# NavCom_Board_2.net
KiCad netlist of a schematic drawn in EAGLE
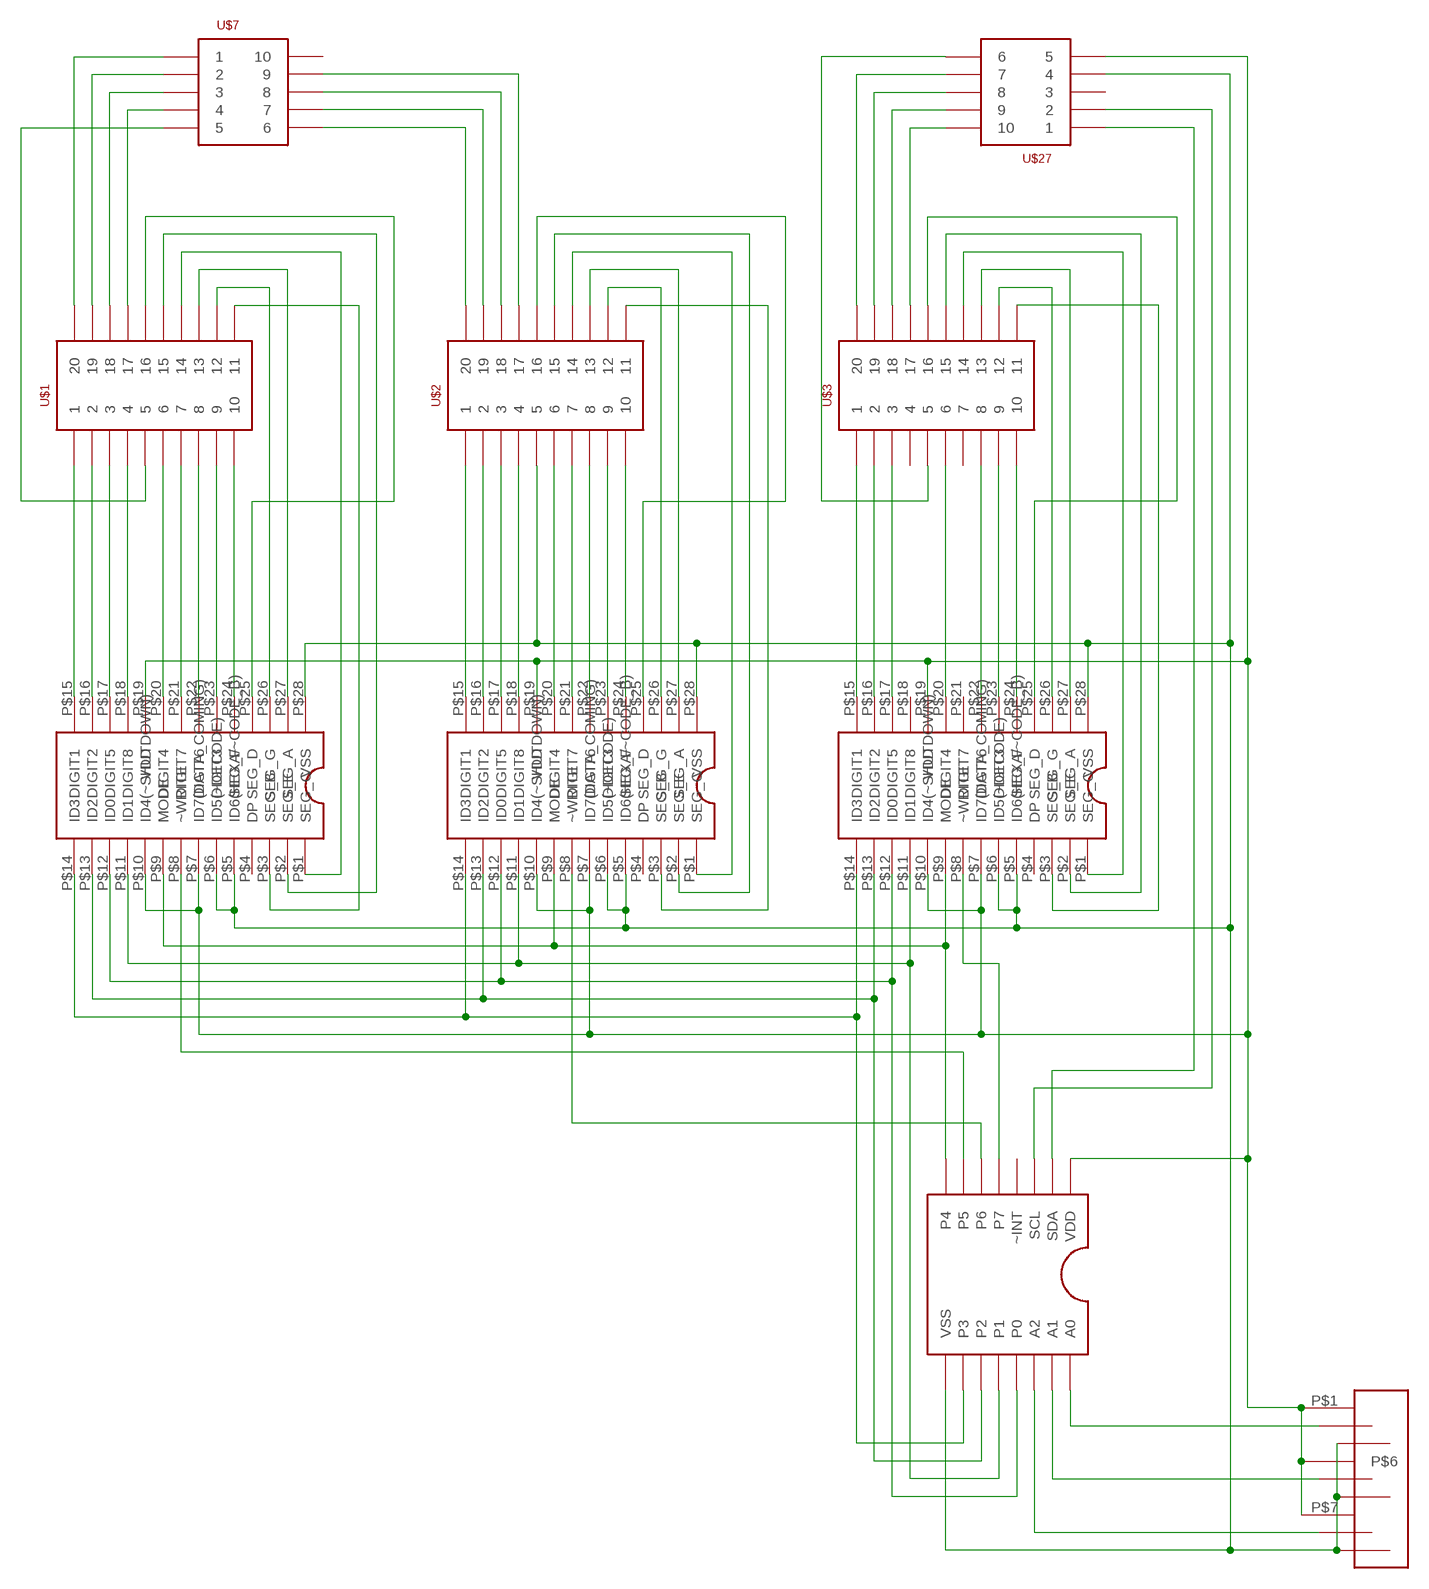
[diagram p0: schematic, sheet 1]

(export (version "E")
  (design (tool "Eeschema 10.0.6"))
  (components
    (comp (ref "U$1")
      (value "LISTA_2X10")
      (footprint "eagle-import:LISTA_2X10")
      (libsource (lib "eagle-import") (part "LISTA_2X10"))
    )
    (comp (ref "U$2")
      (value "LISTA_2X10")
      (footprint "eagle-import:LISTA_2X10")
      (libsource (lib "eagle-import") (part "LISTA_2X10"))
    )
    (comp (ref "U$3")
      (value "LISTA_2X10")
      (footprint "eagle-import:LISTA_2X10")
      (libsource (lib "eagle-import") (part "LISTA_2X10"))
    )
    (comp (ref "U$4")
      (value "ICM7228A")
      (footprint "eagle-import:ICM7228A")
      (libsource (lib "eagle-import") (part "ICM7228A"))
    )
    (comp (ref "U$5")
      (value "ICM7228A")
      (footprint "eagle-import:ICM7228A")
      (libsource (lib "eagle-import") (part "ICM7228A"))
    )
    (comp (ref "U$6")
      (value "ICM7228A")
      (footprint "eagle-import:ICM7228A")
      (libsource (lib "eagle-import") (part "ICM7228A"))
    )
    (comp (ref "U$7")
      (value "LISTA_2X5")
      (footprint "eagle-import:LISTA_2X5")
      (libsource (lib "eagle-import") (part "LISTA_2X5"))
    )
    (comp (ref "U$9")
      (value "PCF8574A")
      (footprint "eagle-import:PCF8574A")
      (libsource (lib "eagle-import") (part "PCF8574A"))
    )
    (comp (ref "U$11")
      (value "ADRESA_0..2")
      (footprint "eagle-import:ADRESA_0..2")
      (libsource (lib "eagle-import") (part "ADRESA_0..2"))
    )
    (comp (ref "U$27")
      (value "LISTA_2X5")
      (footprint "eagle-import:LISTA_2X5")
      (libsource (lib "eagle-import") (part "LISTA_2X5"))
    )
  )
  (nets
    (net (code "1") (name "Net-(U$1-Pad5)") (class "Default")
      (node (ref "U$1") (pin "5") (pinfunction "5_5") (pintype "bidirectional"))
      (node (ref "U$7") (pin "5") (pinfunction "5_5") (pintype "bidirectional"))
    )
    (net (code "2") (name "Net-(U$1-Pad17)") (class "Default")
      (node (ref "U$1") (pin "17") (pinfunction "17_17") (pintype "bidirectional"))
      (node (ref "U$7") (pin "4") (pinfunction "4_4") (pintype "bidirectional"))
    )
    (net (code "3") (name "Net-(U$1-Pad18)") (class "Default")
      (node (ref "U$1") (pin "18") (pinfunction "18_18") (pintype "bidirectional"))
      (node (ref "U$7") (pin "3") (pinfunction "3_3") (pintype "bidirectional"))
    )
    (net (code "4") (name "Net-(U$1-Pad19)") (class "Default")
      (node (ref "U$1") (pin "19") (pinfunction "19_19") (pintype "bidirectional"))
      (node (ref "U$7") (pin "2") (pinfunction "2_2") (pintype "bidirectional"))
    )
    (net (code "5") (name "Net-(U$1-Pad20)") (class "Default")
      (node (ref "U$1") (pin "20") (pinfunction "20_20") (pintype "bidirectional"))
      (node (ref "U$7") (pin "1") (pinfunction "1_1") (pintype "bidirectional"))
    )
    (net (code "6") (name "Net-(U$2-Pad17)") (class "Default")
      (node (ref "U$2") (pin "17") (pinfunction "17_17") (pintype "bidirectional"))
      (node (ref "U$7") (pin "9") (pinfunction "9_9") (pintype "bidirectional"))
    )
    (net (code "7") (name "Net-(U$2-Pad18)") (class "Default")
      (node (ref "U$2") (pin "18") (pinfunction "18_18") (pintype "bidirectional"))
      (node (ref "U$7") (pin "8") (pinfunction "8_8") (pintype "bidirectional"))
    )
    (net (code "8") (name "Net-(U$2-Pad19)") (class "Default")
      (node (ref "U$2") (pin "19") (pinfunction "19_19") (pintype "bidirectional"))
      (node (ref "U$7") (pin "7") (pinfunction "7_7") (pintype "bidirectional"))
    )
    (net (code "9") (name "Net-(U$2-Pad20)") (class "Default")
      (node (ref "U$2") (pin "20") (pinfunction "20_20") (pintype "bidirectional"))
      (node (ref "U$7") (pin "6") (pinfunction "6_6") (pintype "bidirectional"))
    )
    (net (code "10") (name "Net-(U$4-DIGIT1)") (class "Default")
      (node (ref "U$1") (pin "1") (pinfunction "1_1") (pintype "bidirectional"))
      (node (ref "U$4") (pin "P$15") (pinfunction "DIGIT1_P$15") (pintype "bidirectional"))
    )
    (net (code "11") (name "Net-(U$4-DIGIT2)") (class "Default")
      (node (ref "U$1") (pin "2") (pinfunction "2_2") (pintype "bidirectional"))
      (node (ref "U$4") (pin "P$16") (pinfunction "DIGIT2_P$16") (pintype "bidirectional"))
    )
    (net (code "12") (name "Net-(U$4-DIGIT3)") (class "Default")
      (node (ref "U$1") (pin "9") (pinfunction "9_9") (pintype "bidirectional"))
      (node (ref "U$4") (pin "P$23") (pinfunction "DIGIT3_P$23") (pintype "bidirectional"))
    )
    (net (code "13") (name "Net-(U$4-DIGIT4)") (class "Default")
      (node (ref "U$1") (pin "6") (pinfunction "6_6") (pintype "bidirectional"))
      (node (ref "U$4") (pin "P$20") (pinfunction "DIGIT4_P$20") (pintype "bidirectional"))
    )
    (net (code "14") (name "Net-(U$4-DIGIT5)") (class "Default")
      (node (ref "U$1") (pin "3") (pinfunction "3_3") (pintype "bidirectional"))
      (node (ref "U$4") (pin "P$17") (pinfunction "DIGIT5_P$17") (pintype "bidirectional"))
    )
    (net (code "15") (name "Net-(U$4-DIGIT6)") (class "Default")
      (node (ref "U$1") (pin "8") (pinfunction "8_8") (pintype "bidirectional"))
      (node (ref "U$4") (pin "P$22") (pinfunction "DIGIT6_P$22") (pintype "bidirectional"))
    )
    (net (code "16") (name "Net-(U$4-DIGIT7)") (class "Default")
      (node (ref "U$1") (pin "7") (pinfunction "7_7") (pintype "bidirectional"))
      (node (ref "U$4") (pin "P$21") (pinfunction "DIGIT7_P$21") (pintype "bidirectional"))
    )
    (net (code "17") (name "Net-(U$4-DIGIT8)") (class "Default")
      (node (ref "U$1") (pin "4") (pinfunction "4_4") (pintype "bidirectional"))
      (node (ref "U$4") (pin "P$18") (pinfunction "DIGIT8_P$18") (pintype "bidirectional"))
    )
    (net (code "18") (name "Net-(U$4-ID0)") (class "Default")
      (node (ref "U$4") (pin "P$12") (pinfunction "ID0_P$12") (pintype "bidirectional"))
      (node (ref "U$5") (pin "P$12") (pinfunction "ID0_P$12") (pintype "bidirectional"))
      (node (ref "U$6") (pin "P$12") (pinfunction "ID0_P$12") (pintype "bidirectional"))
      (node (ref "U$9") (pin "P0") (pinfunction "P0_P0") (pintype "bidirectional"))
    )
    (net (code "19") (name "Net-(U$4-ID1)") (class "Default")
      (node (ref "U$4") (pin "P$11") (pinfunction "ID1_P$11") (pintype "bidirectional"))
      (node (ref "U$5") (pin "P$11") (pinfunction "ID1_P$11") (pintype "bidirectional"))
      (node (ref "U$6") (pin "P$11") (pinfunction "ID1_P$11") (pintype "bidirectional"))
      (node (ref "U$9") (pin "P1") (pinfunction "P1_P1") (pintype "bidirectional"))
    )
    (net (code "20") (name "Net-(U$4-ID2)") (class "Default")
      (node (ref "U$4") (pin "P$13") (pinfunction "ID2_P$13") (pintype "bidirectional"))
      (node (ref "U$5") (pin "P$13") (pinfunction "ID2_P$13") (pintype "bidirectional"))
      (node (ref "U$6") (pin "P$13") (pinfunction "ID2_P$13") (pintype "bidirectional"))
      (node (ref "U$9") (pin "P2") (pinfunction "P2_P2") (pintype "bidirectional"))
    )
    (net (code "21") (name "Net-(U$4-ID3)") (class "Default")
      (node (ref "U$4") (pin "P$14") (pinfunction "ID3_P$14") (pintype "bidirectional"))
      (node (ref "U$5") (pin "P$14") (pinfunction "ID3_P$14") (pintype "bidirectional"))
      (node (ref "U$6") (pin "P$14") (pinfunction "ID3_P$14") (pintype "bidirectional"))
      (node (ref "U$9") (pin "P3") (pinfunction "P3_P3") (pintype "bidirectional"))
    )
    (net (code "22") (name "Net-(U$4-ID4(~{SHUTDOWN}))") (class "Default")
      (node (ref "U$11") (pin "P$1") (pinfunction "P$1_P$1") (pintype "bidirectional"))
      (node (ref "U$11") (pin "P$6") (pinfunction "P$6_P$6") (pintype "bidirectional"))
      (node (ref "U$11") (pin "P$7") (pinfunction "P$7_P$7") (pintype "bidirectional"))
      (node (ref "U$27") (pin "5") (pinfunction "5_5") (pintype "bidirectional"))
      (node (ref "U$4") (pin "P$10") (pinfunction "ID4(~{SHUTDOWN})_P$10") (pintype "bidirectional"))
      (node (ref "U$4") (pin "P$19") (pinfunction "VDD_P$19") (pintype "bidirectional"))
      (node (ref "U$4") (pin "P$7") (pinfunction "ID7(DATA_COMING)_P$7") (pintype "bidirectional"))
      (node (ref "U$5") (pin "P$10") (pinfunction "ID4(~{SHUTDOWN})_P$10") (pintype "bidirectional"))
      (node (ref "U$5") (pin "P$19") (pinfunction "VDD_P$19") (pintype "bidirectional"))
      (node (ref "U$5") (pin "P$7") (pinfunction "ID7(DATA_COMING)_P$7") (pintype "bidirectional"))
      (node (ref "U$6") (pin "P$10") (pinfunction "ID4(~{SHUTDOWN})_P$10") (pintype "bidirectional"))
      (node (ref "U$6") (pin "P$19") (pinfunction "VDD_P$19") (pintype "bidirectional"))
      (node (ref "U$6") (pin "P$7") (pinfunction "ID7(DATA_COMING)_P$7") (pintype "bidirectional"))
      (node (ref "U$9") (pin "VDD") (pinfunction "VDD_VDD") (pintype "bidirectional"))
    )
    (net (code "23") (name "Net-(U$4-ID5(~{DECODE}))") (class "Default")
      (node (ref "U$11") (pin "P$3") (pinfunction "P$3_P$3") (pintype "bidirectional"))
      (node (ref "U$11") (pin "P$4") (pinfunction "P$4_P$4") (pintype "bidirectional"))
      (node (ref "U$11") (pin "P$9") (pinfunction "P$9_P$9") (pintype "bidirectional"))
      (node (ref "U$2") (pin "5") (pinfunction "5_5") (pintype "bidirectional"))
      (node (ref "U$27") (pin "4") (pinfunction "4_4") (pintype "bidirectional"))
      (node (ref "U$4") (pin "P$28") (pinfunction "VSS_P$28") (pintype "bidirectional"))
      (node (ref "U$4") (pin "P$5") (pinfunction "ID6(HEXA/~{CODE_B})_P$5") (pintype "bidirectional"))
      (node (ref "U$4") (pin "P$6") (pinfunction "ID5(~{DECODE})_P$6") (pintype "bidirectional"))
      (node (ref "U$5") (pin "P$28") (pinfunction "VSS_P$28") (pintype "bidirectional"))
      (node (ref "U$5") (pin "P$5") (pinfunction "ID6(HEXA/~{CODE_B})_P$5") (pintype "bidirectional"))
      (node (ref "U$5") (pin "P$6") (pinfunction "ID5(~{DECODE})_P$6") (pintype "bidirectional"))
      (node (ref "U$6") (pin "P$28") (pinfunction "VSS_P$28") (pintype "bidirectional"))
      (node (ref "U$6") (pin "P$5") (pinfunction "ID6(HEXA/~{CODE_B})_P$5") (pintype "bidirectional"))
      (node (ref "U$6") (pin "P$6") (pinfunction "ID5(~{DECODE})_P$6") (pintype "bidirectional"))
      (node (ref "U$9") (pin "VSS") (pinfunction "VSS_VSS") (pintype "bidirectional"))
    )
    (net (code "24") (name "Net-(U$4-MODE)") (class "Default")
      (node (ref "U$4") (pin "P$9") (pinfunction "MODE_P$9") (pintype "bidirectional"))
      (node (ref "U$5") (pin "P$9") (pinfunction "MODE_P$9") (pintype "bidirectional"))
      (node (ref "U$6") (pin "P$9") (pinfunction "MODE_P$9") (pintype "bidirectional"))
      (node (ref "U$9") (pin "P4") (pinfunction "P4_P4") (pintype "bidirectional"))
    )
    (net (code "25") (name "Net-(U$4-SEG_A)") (class "Default")
      (node (ref "U$1") (pin "13") (pinfunction "13_13") (pintype "bidirectional"))
      (node (ref "U$4") (pin "P$27") (pinfunction "SEG_A_P$27") (pintype "bidirectional"))
    )
    (net (code "26") (name "Net-(U$4-SEG_B)") (class "Default")
      (node (ref "U$1") (pin "11") (pinfunction "11_11") (pintype "bidirectional"))
      (node (ref "U$4") (pin "P$3") (pinfunction "SEG_B_P$3") (pintype "bidirectional"))
    )
    (net (code "27") (name "Net-(U$4-SEG_C)") (class "Default")
      (node (ref "U$1") (pin "14") (pinfunction "14_14") (pintype "bidirectional"))
      (node (ref "U$4") (pin "P$1") (pinfunction "SEG_C_P$1") (pintype "bidirectional"))
    )
    (net (code "28") (name "Net-(U$4-SEG_D)") (class "Default")
      (node (ref "U$1") (pin "16") (pinfunction "16_16") (pintype "bidirectional"))
      (node (ref "U$4") (pin "P$25") (pinfunction "SEG_D_P$25") (pintype "bidirectional"))
    )
    (net (code "29") (name "Net-(U$4-SEG_E)") (class "Default")
      (node (ref "U$1") (pin "15") (pinfunction "15_15") (pintype "bidirectional"))
      (node (ref "U$4") (pin "P$2") (pinfunction "SEG_E_P$2") (pintype "bidirectional"))
    )
    (net (code "30") (name "Net-(U$4-SEG_F)") (class "Default")
      (node (ref "U$1") (pin "10") (pinfunction "10_10") (pintype "bidirectional"))
      (node (ref "U$4") (pin "P$24") (pinfunction "SEG_F_P$24") (pintype "bidirectional"))
    )
    (net (code "31") (name "Net-(U$4-SEG_G)") (class "Default")
      (node (ref "U$1") (pin "12") (pinfunction "12_12") (pintype "bidirectional"))
      (node (ref "U$4") (pin "P$26") (pinfunction "SEG_G_P$26") (pintype "bidirectional"))
    )
    (net (code "32") (name "Net-(U$4-~{WRITE})") (class "Default")
      (node (ref "U$4") (pin "P$8") (pinfunction "~{WRITE}_P$8") (pintype "bidirectional"))
      (node (ref "U$9") (pin "P5") (pinfunction "P5_P5") (pintype "bidirectional"))
    )
    (net (code "33") (name "Net-(U$5-DIGIT1)") (class "Default")
      (node (ref "U$2") (pin "1") (pinfunction "1_1") (pintype "bidirectional"))
      (node (ref "U$5") (pin "P$15") (pinfunction "DIGIT1_P$15") (pintype "bidirectional"))
    )
    (net (code "34") (name "Net-(U$5-DIGIT2)") (class "Default")
      (node (ref "U$2") (pin "2") (pinfunction "2_2") (pintype "bidirectional"))
      (node (ref "U$5") (pin "P$16") (pinfunction "DIGIT2_P$16") (pintype "bidirectional"))
    )
    (net (code "35") (name "Net-(U$5-DIGIT3)") (class "Default")
      (node (ref "U$2") (pin "9") (pinfunction "9_9") (pintype "bidirectional"))
      (node (ref "U$5") (pin "P$23") (pinfunction "DIGIT3_P$23") (pintype "bidirectional"))
    )
    (net (code "36") (name "Net-(U$5-DIGIT4)") (class "Default")
      (node (ref "U$2") (pin "6") (pinfunction "6_6") (pintype "bidirectional"))
      (node (ref "U$5") (pin "P$20") (pinfunction "DIGIT4_P$20") (pintype "bidirectional"))
    )
    (net (code "37") (name "Net-(U$5-DIGIT5)") (class "Default")
      (node (ref "U$2") (pin "3") (pinfunction "3_3") (pintype "bidirectional"))
      (node (ref "U$5") (pin "P$17") (pinfunction "DIGIT5_P$17") (pintype "bidirectional"))
    )
    (net (code "38") (name "Net-(U$5-DIGIT6)") (class "Default")
      (node (ref "U$2") (pin "8") (pinfunction "8_8") (pintype "bidirectional"))
      (node (ref "U$5") (pin "P$22") (pinfunction "DIGIT6_P$22") (pintype "bidirectional"))
    )
    (net (code "39") (name "Net-(U$5-DIGIT7)") (class "Default")
      (node (ref "U$2") (pin "7") (pinfunction "7_7") (pintype "bidirectional"))
      (node (ref "U$5") (pin "P$21") (pinfunction "DIGIT7_P$21") (pintype "bidirectional"))
    )
    (net (code "40") (name "Net-(U$5-DIGIT8)") (class "Default")
      (node (ref "U$2") (pin "4") (pinfunction "4_4") (pintype "bidirectional"))
      (node (ref "U$5") (pin "P$18") (pinfunction "DIGIT8_P$18") (pintype "bidirectional"))
    )
    (net (code "41") (name "Net-(U$5-SEG_A)") (class "Default")
      (node (ref "U$2") (pin "13") (pinfunction "13_13") (pintype "bidirectional"))
      (node (ref "U$5") (pin "P$27") (pinfunction "SEG_A_P$27") (pintype "bidirectional"))
    )
    (net (code "42") (name "Net-(U$5-SEG_B)") (class "Default")
      (node (ref "U$2") (pin "11") (pinfunction "11_11") (pintype "bidirectional"))
      (node (ref "U$5") (pin "P$3") (pinfunction "SEG_B_P$3") (pintype "bidirectional"))
    )
    (net (code "43") (name "Net-(U$5-SEG_C)") (class "Default")
      (node (ref "U$2") (pin "14") (pinfunction "14_14") (pintype "bidirectional"))
      (node (ref "U$5") (pin "P$1") (pinfunction "SEG_C_P$1") (pintype "bidirectional"))
    )
    (net (code "44") (name "Net-(U$5-SEG_D)") (class "Default")
      (node (ref "U$2") (pin "16") (pinfunction "16_16") (pintype "bidirectional"))
      (node (ref "U$5") (pin "P$25") (pinfunction "SEG_D_P$25") (pintype "bidirectional"))
    )
    (net (code "45") (name "Net-(U$5-SEG_E)") (class "Default")
      (node (ref "U$2") (pin "15") (pinfunction "15_15") (pintype "bidirectional"))
      (node (ref "U$5") (pin "P$2") (pinfunction "SEG_E_P$2") (pintype "bidirectional"))
    )
    (net (code "46") (name "Net-(U$5-SEG_F)") (class "Default")
      (node (ref "U$2") (pin "10") (pinfunction "10_10") (pintype "bidirectional"))
      (node (ref "U$5") (pin "P$24") (pinfunction "SEG_F_P$24") (pintype "bidirectional"))
    )
    (net (code "47") (name "Net-(U$5-SEG_G)") (class "Default")
      (node (ref "U$2") (pin "12") (pinfunction "12_12") (pintype "bidirectional"))
      (node (ref "U$5") (pin "P$26") (pinfunction "SEG_G_P$26") (pintype "bidirectional"))
    )
    (net (code "48") (name "Net-(U$5-~{WRITE})") (class "Default")
      (node (ref "U$5") (pin "P$8") (pinfunction "~{WRITE}_P$8") (pintype "bidirectional"))
      (node (ref "U$9") (pin "P6") (pinfunction "P6_P6") (pintype "bidirectional"))
    )
    (net (code "49") (name "Net-(U$6-DIGIT1)") (class "Default")
      (node (ref "U$3") (pin "1") (pinfunction "1_1") (pintype "bidirectional"))
      (node (ref "U$6") (pin "P$15") (pinfunction "DIGIT1_P$15") (pintype "bidirectional"))
    )
    (net (code "50") (name "Net-(U$6-DIGIT2)") (class "Default")
      (node (ref "U$3") (pin "2") (pinfunction "2_2") (pintype "bidirectional"))
      (node (ref "U$6") (pin "P$16") (pinfunction "DIGIT2_P$16") (pintype "bidirectional"))
    )
    (net (code "51") (name "Net-(U$6-DIGIT3)") (class "Default")
      (node (ref "U$3") (pin "9") (pinfunction "9_9") (pintype "bidirectional"))
      (node (ref "U$6") (pin "P$23") (pinfunction "DIGIT3_P$23") (pintype "bidirectional"))
    )
    (net (code "52") (name "Net-(U$6-DIGIT4)") (class "Default")
      (node (ref "U$3") (pin "6") (pinfunction "6_6") (pintype "bidirectional"))
      (node (ref "U$6") (pin "P$20") (pinfunction "DIGIT4_P$20") (pintype "bidirectional"))
    )
    (net (code "53") (name "Net-(U$6-DIGIT5)") (class "Default")
      (node (ref "U$3") (pin "3") (pinfunction "3_3") (pintype "bidirectional"))
      (node (ref "U$6") (pin "P$17") (pinfunction "DIGIT5_P$17") (pintype "bidirectional"))
    )
    (net (code "54") (name "Net-(U$6-DIGIT6)") (class "Default")
      (node (ref "U$3") (pin "8") (pinfunction "8_8") (pintype "bidirectional"))
      (node (ref "U$6") (pin "P$22") (pinfunction "DIGIT6_P$22") (pintype "bidirectional"))
    )
    (net (code "55") (name "Net-(U$6-SEG_A)") (class "Default")
      (node (ref "U$3") (pin "13") (pinfunction "13_13") (pintype "bidirectional"))
      (node (ref "U$6") (pin "P$27") (pinfunction "SEG_A_P$27") (pintype "bidirectional"))
    )
    (net (code "56") (name "Net-(U$6-SEG_B)") (class "Default")
      (node (ref "U$3") (pin "11") (pinfunction "11_11") (pintype "bidirectional"))
      (node (ref "U$6") (pin "P$3") (pinfunction "SEG_B_P$3") (pintype "bidirectional"))
    )
    (net (code "57") (name "Net-(U$6-SEG_C)") (class "Default")
      (node (ref "U$3") (pin "14") (pinfunction "14_14") (pintype "bidirectional"))
      (node (ref "U$6") (pin "P$1") (pinfunction "SEG_C_P$1") (pintype "bidirectional"))
    )
    (net (code "58") (name "Net-(U$6-SEG_D)") (class "Default")
      (node (ref "U$3") (pin "16") (pinfunction "16_16") (pintype "bidirectional"))
      (node (ref "U$6") (pin "P$25") (pinfunction "SEG_D_P$25") (pintype "bidirectional"))
    )
    (net (code "59") (name "Net-(U$6-SEG_E)") (class "Default")
      (node (ref "U$3") (pin "15") (pinfunction "15_15") (pintype "bidirectional"))
      (node (ref "U$6") (pin "P$2") (pinfunction "SEG_E_P$2") (pintype "bidirectional"))
    )
    (net (code "60") (name "Net-(U$6-SEG_F)") (class "Default")
      (node (ref "U$3") (pin "10") (pinfunction "10_10") (pintype "bidirectional"))
      (node (ref "U$6") (pin "P$24") (pinfunction "SEG_F_P$24") (pintype "bidirectional"))
    )
    (net (code "61") (name "Net-(U$6-SEG_G)") (class "Default")
      (node (ref "U$3") (pin "12") (pinfunction "12_12") (pintype "bidirectional"))
      (node (ref "U$6") (pin "P$26") (pinfunction "SEG_G_P$26") (pintype "bidirectional"))
    )
    (net (code "62") (name "Net-(U$6-~{WRITE})") (class "Default")
      (node (ref "U$6") (pin "P$8") (pinfunction "~{WRITE}_P$8") (pintype "bidirectional"))
      (node (ref "U$9") (pin "P7") (pinfunction "P7_P7") (pintype "bidirectional"))
    )
    (net (code "63") (name "Net-(U$11-PadP$2)") (class "Default")
      (node (ref "U$11") (pin "P$2") (pinfunction "P$2_P$2") (pintype "bidirectional"))
      (node (ref "U$9") (pin "A0") (pinfunction "A0_A0") (pintype "bidirectional"))
    )
    (net (code "64") (name "Net-(U$11-PadP$5)") (class "Default")
      (node (ref "U$11") (pin "P$5") (pinfunction "P$5_P$5") (pintype "bidirectional"))
      (node (ref "U$9") (pin "A1") (pinfunction "A1_A1") (pintype "bidirectional"))
    )
    (net (code "65") (name "Net-(U$11-PadP$8)") (class "Default")
      (node (ref "U$11") (pin "P$8") (pinfunction "P$8_P$8") (pintype "bidirectional"))
      (node (ref "U$9") (pin "A2") (pinfunction "A2_A2") (pintype "bidirectional"))
    )
    (net (code "66") (name "Net-(U$27-Pad1)") (class "Default")
      (node (ref "U$27") (pin "1") (pinfunction "1_1") (pintype "bidirectional"))
      (node (ref "U$9") (pin "SDA") (pinfunction "SDA_SDA") (pintype "bidirectional"))
    )
    (net (code "67") (name "Net-(U$27-Pad2)") (class "Default")
      (node (ref "U$27") (pin "2") (pinfunction "2_2") (pintype "bidirectional"))
      (node (ref "U$9") (pin "SCL") (pinfunction "SCL_SCL") (pintype "bidirectional"))
    )
    (net (code "68") (name "Net-(U$27-Pad6)") (class "Default")
      (node (ref "U$27") (pin "6") (pinfunction "6_6") (pintype "bidirectional"))
      (node (ref "U$3") (pin "5") (pinfunction "5_5") (pintype "bidirectional"))
    )
    (net (code "69") (name "Net-(U$27-Pad7)") (class "Default")
      (node (ref "U$27") (pin "7") (pinfunction "7_7") (pintype "bidirectional"))
      (node (ref "U$3") (pin "20") (pinfunction "20_20") (pintype "bidirectional"))
    )
    (net (code "70") (name "Net-(U$27-Pad8)") (class "Default")
      (node (ref "U$27") (pin "8") (pinfunction "8_8") (pintype "bidirectional"))
      (node (ref "U$3") (pin "19") (pinfunction "19_19") (pintype "bidirectional"))
    )
    (net (code "71") (name "Net-(U$27-Pad9)") (class "Default")
      (node (ref "U$27") (pin "9") (pinfunction "9_9") (pintype "bidirectional"))
      (node (ref "U$3") (pin "18") (pinfunction "18_18") (pintype "bidirectional"))
    )
    (net (code "72") (name "Net-(U$27-Pad10)") (class "Default")
      (node (ref "U$27") (pin "10") (pinfunction "10_10") (pintype "bidirectional"))
      (node (ref "U$3") (pin "17") (pinfunction "17_17") (pintype "bidirectional"))
    )
    (net (code "73") (name "unconnected-(U$3-Pad4)") (class "Default")
      (node (ref "U$3") (pin "4") (pinfunction "4_4") (pintype "bidirectional"))
    )
    (net (code "74") (name "unconnected-(U$3-Pad7)") (class "Default")
      (node (ref "U$3") (pin "7") (pinfunction "7_7") (pintype "bidirectional"))
    )
    (net (code "75") (name "unconnected-(U$4-DP-PadP$4)") (class "Default")
      (node (ref "U$4") (pin "P$4") (pinfunction "DP_P$4") (pintype "bidirectional"))
    )
    (net (code "76") (name "unconnected-(U$5-DP-PadP$4)") (class "Default")
      (node (ref "U$5") (pin "P$4") (pinfunction "DP_P$4") (pintype "bidirectional"))
    )
    (net (code "77") (name "unconnected-(U$6-DIGIT7-PadP$21)") (class "Default")
      (node (ref "U$6") (pin "P$21") (pinfunction "DIGIT7_P$21") (pintype "bidirectional"))
    )
    (net (code "78") (name "unconnected-(U$6-DIGIT8-PadP$18)") (class "Default")
      (node (ref "U$6") (pin "P$18") (pinfunction "DIGIT8_P$18") (pintype "bidirectional"))
    )
    (net (code "79") (name "unconnected-(U$6-DP-PadP$4)") (class "Default")
      (node (ref "U$6") (pin "P$4") (pinfunction "DP_P$4") (pintype "bidirectional"))
    )
    (net (code "80") (name "unconnected-(U$7-Pad10)") (class "Default")
      (node (ref "U$7") (pin "10") (pinfunction "10_10") (pintype "bidirectional"))
    )
    (net (code "81") (name "unconnected-(U$9-~{INT}-Pad~INT)") (class "Default")
      (node (ref "U$9") (pin "~INT") (pinfunction "~{INT}_~INT") (pintype "bidirectional"))
    )
    (net (code "82") (name "unconnected-(U$27-Pad3)") (class "Default")
      (node (ref "U$27") (pin "3") (pinfunction "3_3") (pintype "bidirectional"))
    )
  )
)
